# LED.net
KiCad netlist of a schematic drawn in Altium Designer
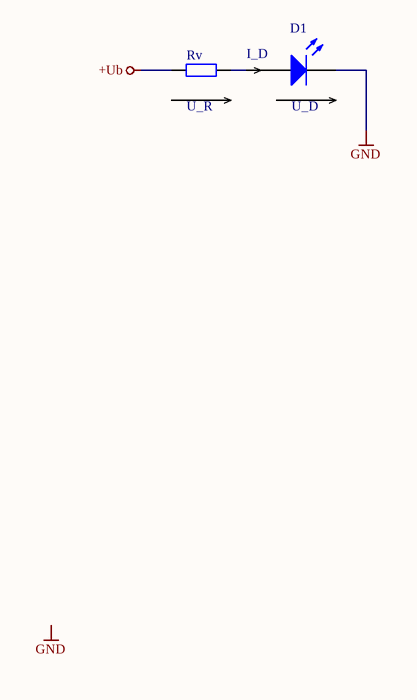
[diagram p0: LED.SchDoc]

(export (version "E")
  (design (tool "Eeschema 10.0.6"))
  (components
    (comp (ref "D1")
      (value "LED BLUE")
      (footprint "LED_5MM - blue")
      (description "Blue SiC LED (Vf=3.4V, If=40mA)")
      (libsource (lib "HTLinn_Opto") (part "LED_BLUE"))
    )
    (comp (ref "Rv")
      (value "1K")
      (footprint "R_0207/RM4")
      (description "Resistor")
      (libsource (lib "HTLInn_RLCQ") (part "R"))
    )
  )
  (nets
    (net (code "1") (name "+Ub") (class "Default")
      (node (ref "Rv") (pin "1") (pinfunction "1_1") (pintype "passive"))
    )
    (net (code "2") (name "GND") (class "Default")
      (node (ref "D1") (pin "K") (pinfunction "K_K") (pintype "passive"))
    )
    (net (code "3") (name "Net-(D1-PadA)") (class "Default")
      (node (ref "D1") (pin "A") (pinfunction "A_A") (pintype "passive"))
      (node (ref "Rv") (pin "2") (pinfunction "2_2") (pintype "passive"))
    )
  )
)
